# pcb_univ_3-101-0-x-rev2.net
KiCad netlist of a schematic drawn in EAGLE
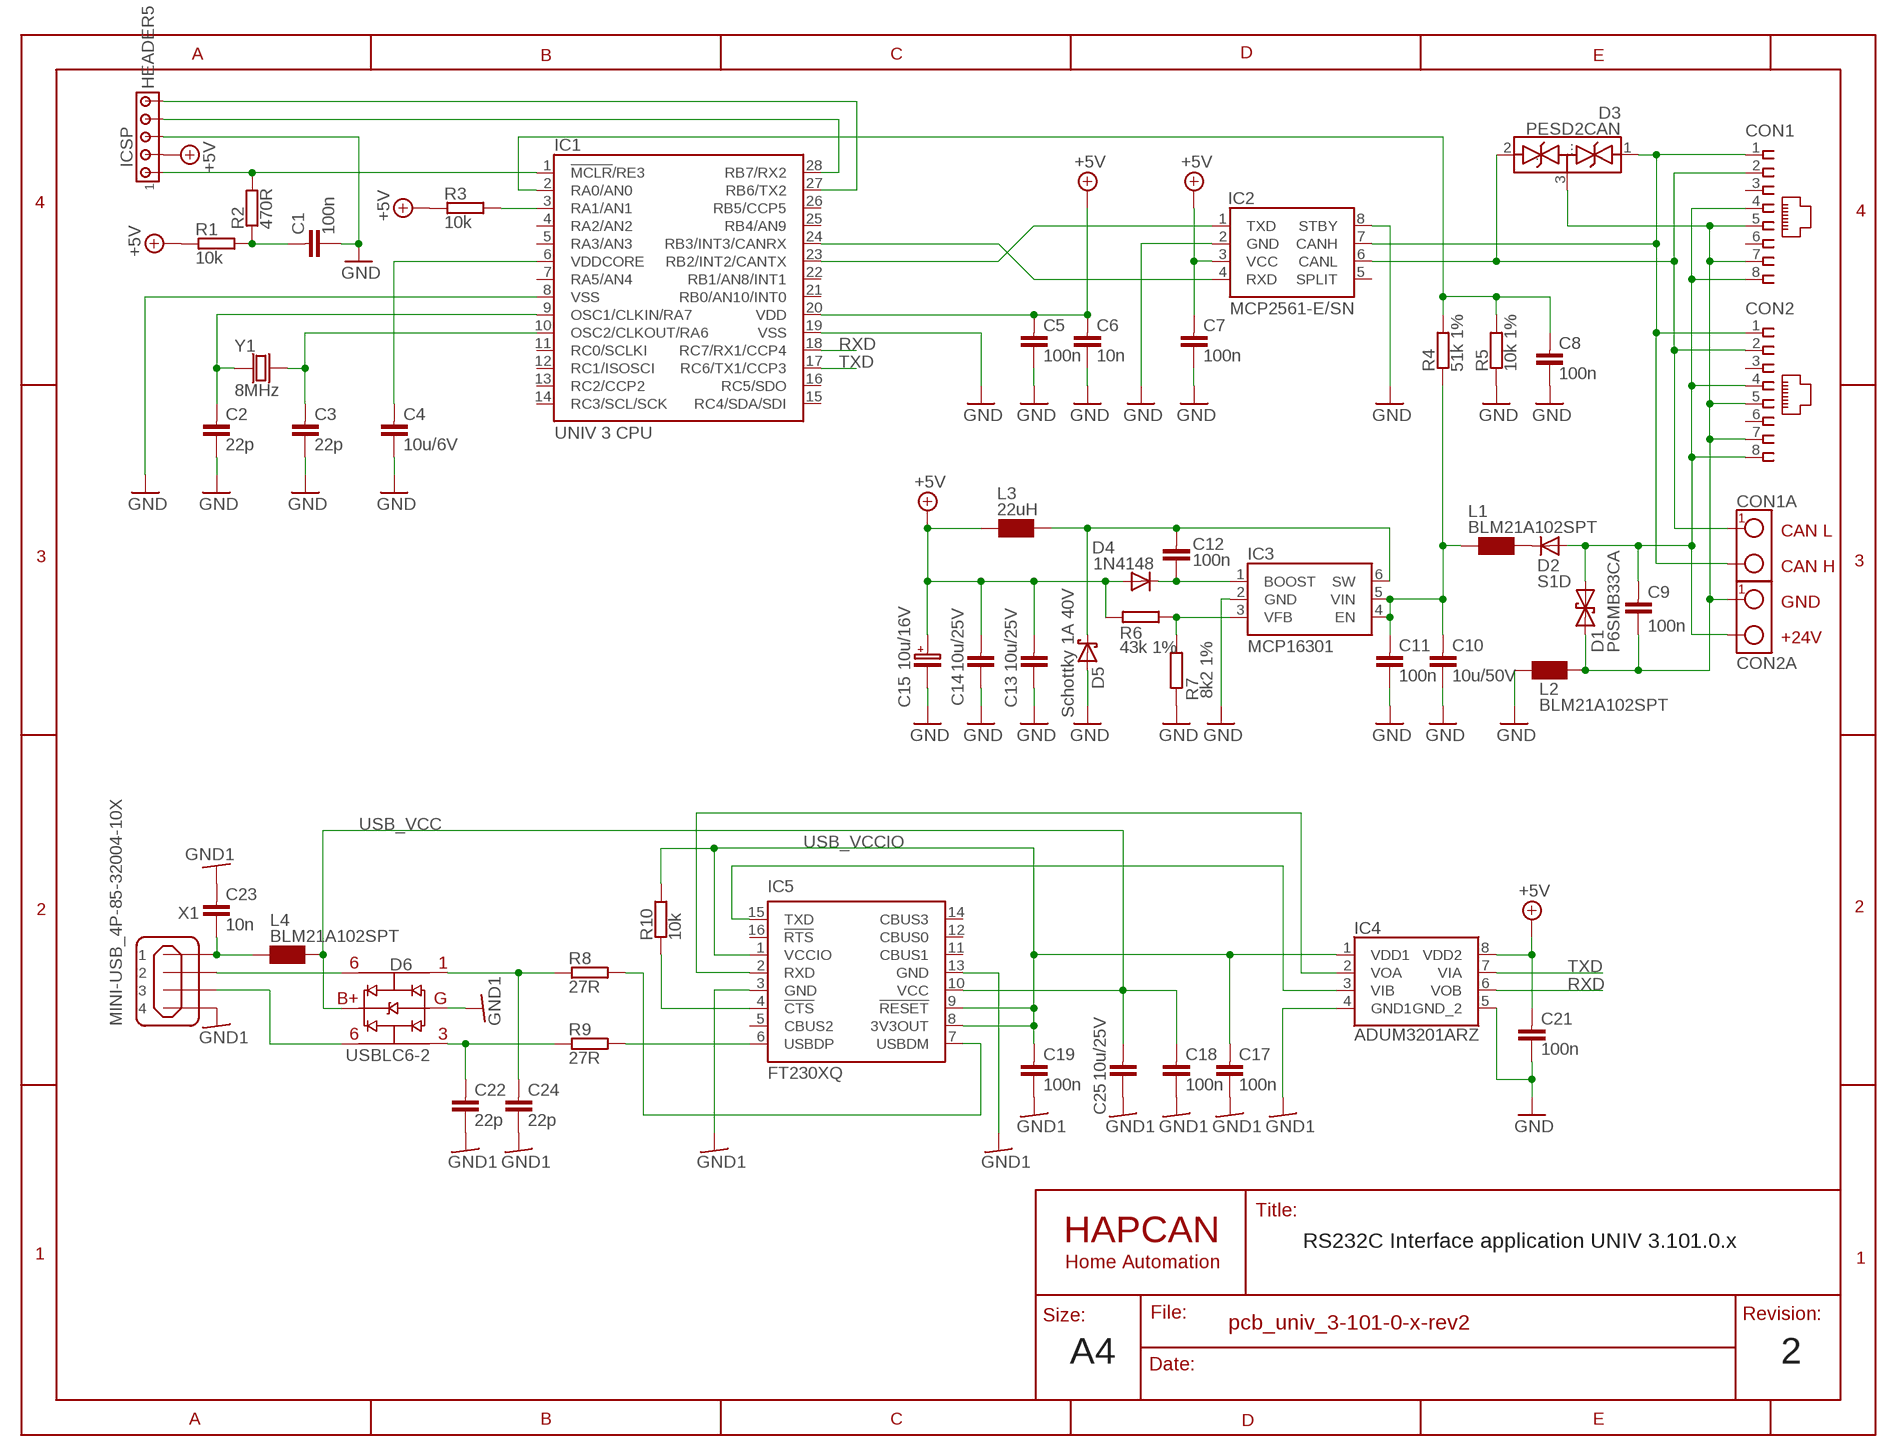
[diagram p0: schematic, sheet 1]

(export (version "E")
  (design (tool "Eeschema 10.0.6"))
  (components
    (comp (ref "C1")
      (value "100n")
      (footprint "eagle-import:0805")
      (libsource (lib "eagle-import") (part "CAPACITOR0805"))
    )
    (comp (ref "C2")
      (value "22p")
      (footprint "eagle-import:0805")
      (libsource (lib "eagle-import") (part "CAPACITOR0805"))
    )
    (comp (ref "C3")
      (value "22p")
      (footprint "eagle-import:0805")
      (libsource (lib "eagle-import") (part "CAPACITOR0805"))
    )
    (comp (ref "C4")
      (value "10u/6V")
      (footprint "eagle-import:0805")
      (libsource (lib "eagle-import") (part "CAPACITOR0805"))
    )
    (comp (ref "C5")
      (value "100n")
      (footprint "eagle-import:0805")
      (libsource (lib "eagle-import") (part "CAPACITOR0805"))
    )
    (comp (ref "C6")
      (value "10n")
      (footprint "eagle-import:0805")
      (libsource (lib "eagle-import") (part "CAPACITOR0805"))
    )
    (comp (ref "C7")
      (value "100n")
      (footprint "eagle-import:0805")
      (libsource (lib "eagle-import") (part "CAPACITOR0805"))
    )
    (comp (ref "C8")
      (value "100n")
      (footprint "eagle-import:0805")
      (libsource (lib "eagle-import") (part "CAPACITOR0805"))
    )
    (comp (ref "C9")
      (value "100n")
      (footprint "eagle-import:0805")
      (libsource (lib "eagle-import") (part "CAPACITOR0805"))
    )
    (comp (ref "C10")
      (value "10u/50V")
      (footprint "eagle-import:1210")
      (libsource (lib "eagle-import") (part "CAPACITOR1210"))
    )
    (comp (ref "C11")
      (value "100n")
      (footprint "eagle-import:0805")
      (libsource (lib "eagle-import") (part "CAPACITOR0805"))
    )
    (comp (ref "C12")
      (value "100n")
      (footprint "eagle-import:0805")
      (libsource (lib "eagle-import") (part "CAPACITOR0805"))
    )
    (comp (ref "C13")
      (value "10u/25V")
      (footprint "eagle-import:1206")
      (libsource (lib "eagle-import") (part "CAPACITOR1206"))
    )
    (comp (ref "C14")
      (value "10u/25V")
      (footprint "eagle-import:1206")
      (libsource (lib "eagle-import") (part "CAPACITOR1206"))
    )
    (comp (ref "C15")
      (value "10u/16V")
      (footprint "eagle-import:SMC_B")
      (libsource (lib "eagle-import") (part "CAPACITOR-POLARIZED-SMC_B"))
    )
    (comp (ref "C17")
      (value "100n")
      (footprint "eagle-import:0805")
      (libsource (lib "eagle-import") (part "CAPACITOR0805"))
    )
    (comp (ref "C18")
      (value "100n")
      (footprint "eagle-import:0805")
      (libsource (lib "eagle-import") (part "CAPACITOR0805"))
    )
    (comp (ref "C19")
      (value "100n")
      (footprint "eagle-import:0805")
      (libsource (lib "eagle-import") (part "CAPACITOR0805"))
    )
    (comp (ref "C21")
      (value "100n")
      (footprint "eagle-import:0805")
      (libsource (lib "eagle-import") (part "CAPACITOR0805"))
    )
    (comp (ref "C22")
      (value "22p")
      (footprint "eagle-import:0805")
      (libsource (lib "eagle-import") (part "CAPACITOR0805"))
    )
    (comp (ref "C23")
      (value "10n")
      (footprint "eagle-import:0805")
      (libsource (lib "eagle-import") (part "CAPACITOR0805"))
    )
    (comp (ref "C24")
      (value "22p")
      (footprint "eagle-import:0805")
      (libsource (lib "eagle-import") (part "CAPACITOR0805"))
    )
    (comp (ref "C25")
      (value "10u/25V")
      (footprint "eagle-import:1206")
      (libsource (lib "eagle-import") (part "CAPACITOR1206"))
    )
    (comp (ref "CON1")
      (value "RJ45-SOCKET")
      (footprint "eagle-import:RJ45-PCB-SOCKET")
      (libsource (lib "eagle-import") (part "RJ45-SOCKET"))
    )
    (comp (ref "CON1A")
      (value "TERMINAL-2")
      (footprint "eagle-import:ARK2-5X10,5MM")
      (libsource (lib "eagle-import") (part "TERMINAL-2-5X10,5MM"))
    )
    (comp (ref "CON2")
      (value "RJ45-SOCKET")
      (footprint "eagle-import:RJ45-PCB-SOCKET")
      (libsource (lib "eagle-import") (part "RJ45-SOCKET"))
    )
    (comp (ref "CON2A")
      (value "TERMINAL-2")
      (footprint "eagle-import:ARK2-5X10,5MM")
      (libsource (lib "eagle-import") (part "TERMINAL-2-5X10,5MM"))
    )
    (comp (ref "D1")
      (value "P6SMB33CA")
      (footprint "eagle-import:DO-214_TRANSIL2")
      (libsource (lib "eagle-import") (part "DIODE_TRANSIL2"))
    )
    (comp (ref "D2")
      (value "S1D")
      (footprint "eagle-import:DO-214")
      (libsource (lib "eagle-import") (part "DIODE_DO-214"))
    )
    (comp (ref "D3")
      (value "PESD2CAN")
      (footprint "eagle-import:SOT-23")
      (libsource (lib "eagle-import") (part "PESD2CANSOT-23"))
    )
    (comp (ref "D4")
      (value "1N4148")
      (footprint "eagle-import:0805")
      (libsource (lib "eagle-import") (part "DIODE_0805"))
    )
    (comp (ref "D5")
      (value "Schottky 1A 40V")
      (footprint "eagle-import:DO-214")
      (libsource (lib "eagle-import") (part "DIODE_TRANSIL1_DO214"))
    )
    (comp (ref "D6")
      (value "USBLC6-2")
      (footprint "eagle-import:SOT23-6L")
      (description "USB ESD protection")
      (fields (field (name "MFR_PART_NO") "USBLC6-2SC6"))
      (libsource (lib "eagle-import") (part "USBLC6-2"))
    )
    (comp (ref "IC1")
      (value "UNIV 3 CPU")
      (footprint "eagle-import:UNIV3CPU")
      (libsource (lib "eagle-import") (part "UNIV3CPU-I/SO"))
    )
    (comp (ref "IC2")
      (value "MCP2561-E/SN")
      (footprint "eagle-import:SO-08")
      (libsource (lib "eagle-import") (part "MCP2561-E/SN"))
    )
    (comp (ref "IC3")
      (value "MCP16301")
      (footprint "eagle-import:SOT-23-6")
      (libsource (lib "eagle-import") (part "MCP16301SOT23-6"))
    )
    (comp (ref "IC4")
      (value "ADUM3201ARZ")
      (footprint "eagle-import:SOIC127P600X175-8N")
      (fields (field (name "MF") "Analog Devices"))
      (libsource (lib "eagle-import") (part "ADUM3201ARZ"))
    )
    (comp (ref "IC5")
      (value "FT230XQ")
      (footprint "eagle-import:QFN16")
      (libsource (lib "eagle-import") (part "FT230XQ"))
    )
    (comp (ref "ICSP")
      (value "HEADER5")
      (footprint "eagle-import:SIP-5")
      (libsource (lib "eagle-import") (part "HEADER5"))
    )
    (comp (ref "L1")
      (value "BLM21A102SPT")
      (footprint "eagle-import:0805")
      (libsource (lib "eagle-import") (part "CHOKE0805"))
    )
    (comp (ref "L2")
      (value "BLM21A102SPT")
      (footprint "eagle-import:0805")
      (libsource (lib "eagle-import") (part "CHOKE0805"))
    )
    (comp (ref "L3")
      (value "22uH")
      (footprint "eagle-import:CHOKE-DER0705")
      (libsource (lib "eagle-import") (part "CHOKEDER0705"))
    )
    (comp (ref "L4")
      (value "BLM21A102SPT")
      (footprint "eagle-import:0805")
      (libsource (lib "eagle-import") (part "CHOKE0805"))
    )
    (comp (ref "R1")
      (value "10k")
      (footprint "eagle-import:0805")
      (libsource (lib "eagle-import") (part "RESISTOR0805"))
    )
    (comp (ref "R2")
      (value "470R")
      (footprint "eagle-import:0805")
      (libsource (lib "eagle-import") (part "RESISTOR0805"))
    )
    (comp (ref "R3")
      (value "10k")
      (footprint "eagle-import:0805")
      (libsource (lib "eagle-import") (part "RESISTOR0805"))
    )
    (comp (ref "R4")
      (value "51k 1%")
      (footprint "eagle-import:0805")
      (libsource (lib "eagle-import") (part "RESISTOR0805"))
    )
    (comp (ref "R5")
      (value "10k 1%")
      (footprint "eagle-import:0805")
      (libsource (lib "eagle-import") (part "RESISTOR0805"))
    )
    (comp (ref "R6")
      (value "43k 1%")
      (footprint "eagle-import:0805")
      (libsource (lib "eagle-import") (part "RESISTOR0805"))
    )
    (comp (ref "R7")
      (value "8k2 1%")
      (footprint "eagle-import:0805")
      (libsource (lib "eagle-import") (part "RESISTOR0805"))
    )
    (comp (ref "R8")
      (value "27R")
      (footprint "eagle-import:0805")
      (libsource (lib "eagle-import") (part "RESISTOR0805"))
    )
    (comp (ref "R9")
      (value "27R")
      (footprint "eagle-import:0805")
      (libsource (lib "eagle-import") (part "RESISTOR0805"))
    )
    (comp (ref "R10")
      (value "10k")
      (footprint "eagle-import:0805")
      (libsource (lib "eagle-import") (part "RESISTOR0805"))
    )
    (comp (ref "X1")
      (value "MINI-USB_4P-85-32004-10X")
      (footprint "eagle-import:85-32004-10X")
      (libsource (lib "eagle-import") (part "MINI-USB_4P-85-32004-10X"))
    )
    (comp (ref "Y1")
      (value "8MHz")
      (footprint "eagle-import:CRYSTAL-HC49V")
      (libsource (lib "eagle-import") (part "CRYSTAL-HC49V"))
    )
  )
  (nets
    (net (code "1") (name "+5V") (class "Default")
      (node (ref "C13") (pin "1") (pinfunction "1_1") (pintype "passive"))
      (node (ref "C14") (pin "1") (pinfunction "1_1") (pintype "passive"))
      (node (ref "C15") (pin "+") (pinfunction "1_+") (pintype "passive"))
      (node (ref "C21") (pin "1") (pinfunction "1_1") (pintype "passive"))
      (node (ref "C5") (pin "1") (pinfunction "1_1") (pintype "passive"))
      (node (ref "C6") (pin "1") (pinfunction "1_1") (pintype "passive"))
      (node (ref "C7") (pin "1") (pinfunction "1_1") (pintype "passive"))
      (node (ref "D4") (pin "2") (pinfunction "A_2") (pintype "passive"))
      (node (ref "IC1") (pin "20") (pinfunction "VDD_20") (pintype "bidirectional"))
      (node (ref "IC2") (pin "3") (pinfunction "VCC_3") (pintype "bidirectional"))
      (node (ref "IC4") (pin "8") (pinfunction "VDD2_8") (pintype "bidirectional"))
      (node (ref "ICSP") (pin "2") (pinfunction "2_2") (pintype "passive"))
      (node (ref "L3") (pin "1") (pinfunction "1_1") (pintype "passive"))
      (node (ref "R1") (pin "1") (pinfunction "1_1") (pintype "passive"))
      (node (ref "R3") (pin "1") (pinfunction "1_1") (pintype "passive"))
      (node (ref "R6") (pin "1") (pinfunction "1_1") (pintype "passive"))
    )
    (net (code "2") (name "/RXD") (class "Default")
      (node (ref "IC1") (pin "18") (pinfunction "RC7/RX1/CCP4_18") (pintype "bidirectional"))
      (node (ref "IC4") (pin "6") (pinfunction "VOB_6") (pintype "bidirectional"))
    )
    (net (code "3") (name "/TXD") (class "Default")
      (node (ref "IC1") (pin "17") (pinfunction "RC6/TX1/CCP3_17") (pintype "bidirectional"))
      (node (ref "IC4") (pin "7") (pinfunction "VIA_7") (pintype "bidirectional"))
    )
    (net (code "4") (name "/USB_VCC") (class "Default")
      (node (ref "C18") (pin "1") (pinfunction "1_1") (pintype "passive"))
      (node (ref "C25") (pin "1") (pinfunction "1_1") (pintype "passive"))
      (node (ref "D6") (pin "5") (pinfunction "B+_5") (pintype "bidirectional"))
      (node (ref "IC5") (pin "10") (pinfunction "VCC_10") (pintype "power_in"))
      (node (ref "L4") (pin "1") (pinfunction "1_1") (pintype "passive"))
    )
    (net (code "5") (name "/USB_VCCIO") (class "Default")
      (node (ref "C17") (pin "1") (pinfunction "1_1") (pintype "passive"))
      (node (ref "C19") (pin "1") (pinfunction "1_1") (pintype "passive"))
      (node (ref "IC4") (pin "1") (pinfunction "VDD1_1") (pintype "bidirectional"))
      (node (ref "IC5") (pin "1") (pinfunction "VCCIO_1") (pintype "power_in"))
      (node (ref "IC5") (pin "8") (pinfunction "3V3OUT_8") (pintype "output"))
      (node (ref "IC5") (pin "9") (pinfunction "~{RESET}_9") (pintype "input"))
      (node (ref "R10") (pin "2") (pinfunction "2_2") (pintype "passive"))
    )
    (net (code "6") (name "GND") (class "Default")
      (node (ref "C1") (pin "2") (pinfunction "2_2") (pintype "passive"))
      (node (ref "C10") (pin "2") (pinfunction "2_2") (pintype "passive"))
      (node (ref "C11") (pin "2") (pinfunction "2_2") (pintype "passive"))
      (node (ref "C13") (pin "2") (pinfunction "2_2") (pintype "passive"))
      (node (ref "C14") (pin "2") (pinfunction "2_2") (pintype "passive"))
      (node (ref "C15") (pin "-") (pinfunction "2_-") (pintype "passive"))
      (node (ref "C2") (pin "2") (pinfunction "2_2") (pintype "passive"))
      (node (ref "C21") (pin "2") (pinfunction "2_2") (pintype "passive"))
      (node (ref "C3") (pin "2") (pinfunction "2_2") (pintype "passive"))
      (node (ref "C4") (pin "2") (pinfunction "2_2") (pintype "passive"))
      (node (ref "C5") (pin "2") (pinfunction "2_2") (pintype "passive"))
      (node (ref "C6") (pin "2") (pinfunction "2_2") (pintype "passive"))
      (node (ref "C7") (pin "2") (pinfunction "2_2") (pintype "passive"))
      (node (ref "C8") (pin "2") (pinfunction "2_2") (pintype "passive"))
      (node (ref "D5") (pin "A") (pinfunction "A_A") (pintype "passive"))
      (node (ref "IC1") (pin "19") (pinfunction "VSS_19") (pintype "bidirectional"))
      (node (ref "IC1") (pin "8") (pinfunction "VSS_8") (pintype "bidirectional"))
      (node (ref "IC2") (pin "2") (pinfunction "GND_2") (pintype "bidirectional"))
      (node (ref "IC2") (pin "8") (pinfunction "STBY_8") (pintype "bidirectional"))
      (node (ref "IC3") (pin "2") (pinfunction "GND_2") (pintype "bidirectional"))
      (node (ref "IC4") (pin "5") (pinfunction "GND_2_5") (pintype "bidirectional"))
      (node (ref "ICSP") (pin "3") (pinfunction "3_3") (pintype "passive"))
      (node (ref "L2") (pin "1") (pinfunction "1_1") (pintype "passive"))
      (node (ref "R5") (pin "1") (pinfunction "1_1") (pintype "passive"))
      (node (ref "R7") (pin "1") (pinfunction "1_1") (pintype "passive"))
    )
    (net (code "7") (name "GND1") (class "Default")
      (node (ref "C17") (pin "2") (pinfunction "2_2") (pintype "passive"))
      (node (ref "C18") (pin "2") (pinfunction "2_2") (pintype "passive"))
      (node (ref "C19") (pin "2") (pinfunction "2_2") (pintype "passive"))
      (node (ref "C22") (pin "2") (pinfunction "2_2") (pintype "passive"))
      (node (ref "C23") (pin "1") (pinfunction "1_1") (pintype "passive"))
      (node (ref "C24") (pin "2") (pinfunction "2_2") (pintype "passive"))
      (node (ref "C25") (pin "2") (pinfunction "2_2") (pintype "passive"))
      (node (ref "D6") (pin "2") (pinfunction "G_2") (pintype "bidirectional"))
      (node (ref "IC4") (pin "4") (pinfunction "GND1_4") (pintype "bidirectional"))
      (node (ref "IC5") (pin "13") (pinfunction "GND_13") (pintype "power_in"))
      (node (ref "IC5") (pin "3") (pinfunction "GND_3") (pintype "power_in"))
      (node (ref "X1") (pin "4") (pinfunction "4_4") (pintype "passive"))
    )
    (net (code "8") (name "Net-(C1-Pad1)") (class "Default")
      (node (ref "C1") (pin "1") (pinfunction "1_1") (pintype "passive"))
      (node (ref "R1") (pin "2") (pinfunction "2_2") (pintype "passive"))
      (node (ref "R2") (pin "1") (pinfunction "1_1") (pintype "passive"))
    )
    (net (code "9") (name "Net-(C22-Pad1)") (class "Default")
      (node (ref "C22") (pin "1") (pinfunction "1_1") (pintype "passive"))
      (node (ref "D6") (pin "3") (pinfunction "3_3") (pintype "bidirectional"))
      (node (ref "R9") (pin "1") (pinfunction "1_1") (pintype "passive"))
    )
    (net (code "10") (name "Net-(C23-Pad2)") (class "Default")
      (node (ref "C23") (pin "2") (pinfunction "2_2") (pintype "passive"))
      (node (ref "L4") (pin "2") (pinfunction "2_2") (pintype "passive"))
      (node (ref "X1") (pin "1") (pinfunction "1_1") (pintype "passive"))
    )
    (net (code "11") (name "Net-(C24-Pad1)") (class "Default")
      (node (ref "C24") (pin "1") (pinfunction "1_1") (pintype "passive"))
      (node (ref "D6") (pin "1") (pinfunction "1_1") (pintype "bidirectional"))
      (node (ref "R8") (pin "1") (pinfunction "1_1") (pintype "passive"))
    )
    (net (code "12") (name "Net-(D1-1)") (class "Default")
      (node (ref "C9") (pin "1") (pinfunction "1_1") (pintype "passive"))
      (node (ref "CON1") (pin "4") (pinfunction "4_4") (pintype "passive"))
      (node (ref "CON1") (pin "8") (pinfunction "8_8") (pintype "passive"))
      (node (ref "CON2") (pin "4") (pinfunction "4_4") (pintype "passive"))
      (node (ref "CON2") (pin "8") (pinfunction "8_8") (pintype "passive"))
      (node (ref "CON2A") (pin "2") (pinfunction "2_2") (pintype "passive"))
      (node (ref "D1") (pin "A") (pinfunction "1_A") (pintype "passive"))
      (node (ref "D2") (pin "A") (pinfunction "A_A") (pintype "passive"))
    )
    (net (code "13") (name "Net-(D1-2)") (class "Default")
      (node (ref "C9") (pin "2") (pinfunction "2_2") (pintype "passive"))
      (node (ref "CON1") (pin "5") (pinfunction "5_5") (pintype "passive"))
      (node (ref "CON1") (pin "7") (pinfunction "7_7") (pintype "passive"))
      (node (ref "CON2") (pin "5") (pinfunction "5_5") (pintype "passive"))
      (node (ref "CON2") (pin "7") (pinfunction "7_7") (pintype "passive"))
      (node (ref "CON2A") (pin "1") (pinfunction "1_1") (pintype "passive"))
      (node (ref "D1") (pin "C") (pinfunction "2_C") (pintype "passive"))
      (node (ref "D3") (pin "3") (pinfunction "..._3") (pintype "bidirectional"))
      (node (ref "L2") (pin "2") (pinfunction "2_2") (pintype "passive"))
    )
    (net (code "14") (name "Net-(D2-PadC)") (class "Default")
      (node (ref "D2") (pin "C") (pinfunction "C_C") (pintype "passive"))
      (node (ref "L1") (pin "2") (pinfunction "2_2") (pintype "passive"))
    )
    (net (code "15") (name "Net-(D3-.)") (class "Default")
      (node (ref "CON1") (pin "1") (pinfunction "1_1") (pintype "passive"))
      (node (ref "CON1A") (pin "2") (pinfunction "2_2") (pintype "passive"))
      (node (ref "CON2") (pin "1") (pinfunction "1_1") (pintype "passive"))
      (node (ref "D3") (pin "1") (pinfunction "._1") (pintype "bidirectional"))
      (node (ref "IC2") (pin "7") (pinfunction "CANH_7") (pintype "bidirectional"))
    )
    (net (code "16") (name "Net-(D3-..)") (class "Default")
      (node (ref "CON1") (pin "2") (pinfunction "2_2") (pintype "passive"))
      (node (ref "CON1A") (pin "1") (pinfunction "1_1") (pintype "passive"))
      (node (ref "CON2") (pin "2") (pinfunction "2_2") (pintype "passive"))
      (node (ref "D3") (pin "2") (pinfunction ".._2") (pintype "bidirectional"))
      (node (ref "IC2") (pin "6") (pinfunction "CANL_6") (pintype "bidirectional"))
    )
    (net (code "17") (name "Net-(D4-C)") (class "Default")
      (node (ref "C12") (pin "2") (pinfunction "2_2") (pintype "passive"))
      (node (ref "D4") (pin "1") (pinfunction "C_1") (pintype "passive"))
      (node (ref "IC3") (pin "1") (pinfunction "BOOST_1") (pintype "bidirectional"))
    )
    (net (code "18") (name "Net-(D6-Pad4)") (class "Default")
      (node (ref "D6") (pin "4") (pinfunction "4_4") (pintype "bidirectional"))
      (node (ref "X1") (pin "3") (pinfunction "3_3") (pintype "passive"))
    )
    (net (code "19") (name "Net-(D6-Pad6)") (class "Default")
      (node (ref "D6") (pin "6") (pinfunction "6_6") (pintype "bidirectional"))
      (node (ref "X1") (pin "2") (pinfunction "2_2") (pintype "passive"))
    )
    (net (code "20") (name "Net-(IC1-OSC1{slash}CLKIN{slash}RA7)") (class "Default")
      (node (ref "C2") (pin "1") (pinfunction "1_1") (pintype "passive"))
      (node (ref "IC1") (pin "9") (pinfunction "OSC1/CLKIN/RA7_9") (pintype "bidirectional"))
      (node (ref "Y1") (pin "1") (pinfunction "1_1") (pintype "passive"))
    )
    (net (code "21") (name "Net-(IC1-OSC2{slash}CLKOUT{slash}RA6)") (class "Default")
      (node (ref "C3") (pin "1") (pinfunction "1_1") (pintype "passive"))
      (node (ref "IC1") (pin "10") (pinfunction "OSC2/CLKOUT/RA6_10") (pintype "bidirectional"))
      (node (ref "Y1") (pin "2") (pinfunction "2_2") (pintype "passive"))
    )
    (net (code "22") (name "Net-(IC1-RA0{slash}AN0)") (class "Default")
      (node (ref "C8") (pin "1") (pinfunction "1_1") (pintype "passive"))
      (node (ref "IC1") (pin "2") (pinfunction "RA0/AN0_2") (pintype "bidirectional"))
      (node (ref "R4") (pin "2") (pinfunction "2_2") (pintype "passive"))
      (node (ref "R5") (pin "2") (pinfunction "2_2") (pintype "passive"))
    )
    (net (code "23") (name "Net-(IC1-RA1{slash}AN1)") (class "Default")
      (node (ref "IC1") (pin "3") (pinfunction "RA1/AN1_3") (pintype "bidirectional"))
      (node (ref "R3") (pin "2") (pinfunction "2_2") (pintype "passive"))
    )
    (net (code "24") (name "Net-(IC1-RB2{slash}INT2{slash}CANTX)") (class "Default")
      (node (ref "IC1") (pin "23") (pinfunction "RB2/INT2/CANTX_23") (pintype "bidirectional"))
      (node (ref "IC2") (pin "1") (pinfunction "TXD_1") (pintype "bidirectional"))
    )
    (net (code "25") (name "Net-(IC1-RB3{slash}INT3{slash}CANRX)") (class "Default")
      (node (ref "IC1") (pin "24") (pinfunction "RB3/INT3/CANRX_24") (pintype "bidirectional"))
      (node (ref "IC2") (pin "4") (pinfunction "RXD_4") (pintype "bidirectional"))
    )
    (net (code "26") (name "Net-(IC1-RB6{slash}TX2)") (class "Default")
      (node (ref "IC1") (pin "27") (pinfunction "RB6/TX2_27") (pintype "bidirectional"))
      (node (ref "ICSP") (pin "5") (pinfunction "5_5") (pintype "passive"))
    )
    (net (code "27") (name "Net-(IC1-RB7{slash}RX2)") (class "Default")
      (node (ref "IC1") (pin "28") (pinfunction "RB7/RX2_28") (pintype "bidirectional"))
      (node (ref "ICSP") (pin "4") (pinfunction "4_4") (pintype "passive"))
    )
    (net (code "28") (name "Net-(IC1-VDDCORE)") (class "Default")
      (node (ref "C4") (pin "1") (pinfunction "1_1") (pintype "passive"))
      (node (ref "IC1") (pin "6") (pinfunction "VDDCORE_6") (pintype "bidirectional"))
    )
    (net (code "29") (name "Net-(IC1-~{MCLR}{slash}RE3)") (class "Default")
      (node (ref "IC1") (pin "1") (pinfunction "~{MCLR}/RE3_1") (pintype "bidirectional"))
      (node (ref "ICSP") (pin "1") (pinfunction "1_1") (pintype "passive"))
      (node (ref "R2") (pin "2") (pinfunction "2_2") (pintype "passive"))
    )
    (net (code "30") (name "Net-(IC3-EN)") (class "Default")
      (node (ref "C10") (pin "1") (pinfunction "1_1") (pintype "passive"))
      (node (ref "C11") (pin "1") (pinfunction "1_1") (pintype "passive"))
      (node (ref "IC3") (pin "4") (pinfunction "EN_4") (pintype "bidirectional"))
      (node (ref "IC3") (pin "5") (pinfunction "VIN_5") (pintype "bidirectional"))
      (node (ref "L1") (pin "1") (pinfunction "1_1") (pintype "passive"))
      (node (ref "R4") (pin "1") (pinfunction "1_1") (pintype "passive"))
    )
    (net (code "31") (name "Net-(IC3-SW)") (class "Default")
      (node (ref "C12") (pin "1") (pinfunction "1_1") (pintype "passive"))
      (node (ref "D5") (pin "C") (pinfunction "C_C") (pintype "passive"))
      (node (ref "IC3") (pin "6") (pinfunction "SW_6") (pintype "bidirectional"))
      (node (ref "L3") (pin "2") (pinfunction "2_2") (pintype "passive"))
    )
    (net (code "32") (name "Net-(IC3-VFB)") (class "Default")
      (node (ref "IC3") (pin "3") (pinfunction "VFB_3") (pintype "bidirectional"))
      (node (ref "R6") (pin "2") (pinfunction "2_2") (pintype "passive"))
      (node (ref "R7") (pin "2") (pinfunction "2_2") (pintype "passive"))
    )
    (net (code "33") (name "Net-(IC4-VIB)") (class "Default")
      (node (ref "IC4") (pin "3") (pinfunction "VIB_3") (pintype "bidirectional"))
      (node (ref "IC5") (pin "15") (pinfunction "TXD_15") (pintype "output"))
    )
    (net (code "34") (name "Net-(IC4-VOA)") (class "Default")
      (node (ref "IC4") (pin "2") (pinfunction "VOA_2") (pintype "bidirectional"))
      (node (ref "IC5") (pin "2") (pinfunction "RXD_2") (pintype "input"))
    )
    (net (code "35") (name "Net-(IC5-USBDM)") (class "Default")
      (node (ref "IC5") (pin "7") (pinfunction "USBDM_7") (pintype "input"))
      (node (ref "R8") (pin "2") (pinfunction "2_2") (pintype "passive"))
    )
    (net (code "36") (name "Net-(IC5-USBDP)") (class "Default")
      (node (ref "IC5") (pin "6") (pinfunction "USBDP_6") (pintype "input"))
      (node (ref "R9") (pin "2") (pinfunction "2_2") (pintype "passive"))
    )
    (net (code "37") (name "Net-(IC5-~{CTS})") (class "Default")
      (node (ref "IC5") (pin "4") (pinfunction "~{CTS}_4") (pintype "input"))
      (node (ref "R10") (pin "1") (pinfunction "1_1") (pintype "passive"))
    )
    (net (code "38") (name "unconnected-(CON1-Pad3)") (class "Default")
      (node (ref "CON1") (pin "3") (pinfunction "3_3") (pintype "passive"))
    )
    (net (code "39") (name "unconnected-(CON1-Pad6)") (class "Default")
      (node (ref "CON1") (pin "6") (pinfunction "6_6") (pintype "passive"))
    )
    (net (code "40") (name "unconnected-(CON2-Pad3)") (class "Default")
      (node (ref "CON2") (pin "3") (pinfunction "3_3") (pintype "passive"))
    )
    (net (code "41") (name "unconnected-(CON2-Pad6)") (class "Default")
      (node (ref "CON2") (pin "6") (pinfunction "6_6") (pintype "passive"))
    )
    (net (code "42") (name "unconnected-(IC1-RA2{slash}AN2-Pad4)") (class "Default")
      (node (ref "IC1") (pin "4") (pinfunction "RA2/AN2_4") (pintype "bidirectional"))
    )
    (net (code "43") (name "unconnected-(IC1-RA3{slash}AN3-Pad5)") (class "Default")
      (node (ref "IC1") (pin "5") (pinfunction "RA3/AN3_5") (pintype "bidirectional"))
    )
    (net (code "44") (name "unconnected-(IC1-RA5{slash}AN4-Pad7)") (class "Default")
      (node (ref "IC1") (pin "7") (pinfunction "RA5/AN4_7") (pintype "bidirectional"))
    )
    (net (code "45") (name "unconnected-(IC1-RB0{slash}AN10{slash}INT0-Pad21)") (class "Default")
      (node (ref "IC1") (pin "21") (pinfunction "RB0/AN10/INT0_21") (pintype "bidirectional"))
    )
    (net (code "46") (name "unconnected-(IC1-RB1{slash}AN8{slash}INT1-Pad22)") (class "Default")
      (node (ref "IC1") (pin "22") (pinfunction "RB1/AN8/INT1_22") (pintype "bidirectional"))
    )
    (net (code "47") (name "unconnected-(IC1-RB4{slash}AN9-Pad25)") (class "Default")
      (node (ref "IC1") (pin "25") (pinfunction "RB4/AN9_25") (pintype "bidirectional"))
    )
    (net (code "48") (name "unconnected-(IC1-RB5{slash}CCP5-Pad26)") (class "Default")
      (node (ref "IC1") (pin "26") (pinfunction "RB5/CCP5_26") (pintype "bidirectional"))
    )
    (net (code "49") (name "unconnected-(IC1-RC0{slash}SCLKI-Pad11)") (class "Default")
      (node (ref "IC1") (pin "11") (pinfunction "RC0/SCLKI_11") (pintype "bidirectional"))
    )
    (net (code "50") (name "unconnected-(IC1-RC1{slash}ISOSCI-Pad12)") (class "Default")
      (node (ref "IC1") (pin "12") (pinfunction "RC1/ISOSCI_12") (pintype "bidirectional"))
    )
    (net (code "51") (name "unconnected-(IC1-RC2{slash}CCP2-Pad13)") (class "Default")
      (node (ref "IC1") (pin "13") (pinfunction "RC2/CCP2_13") (pintype "bidirectional"))
    )
    (net (code "52") (name "unconnected-(IC1-RC3{slash}SCL{slash}SCK-Pad14)") (class "Default")
      (node (ref "IC1") (pin "14") (pinfunction "RC3/SCL/SCK_14") (pintype "bidirectional"))
    )
    (net (code "53") (name "unconnected-(IC1-RC4{slash}SDA{slash}SDI-Pad15)") (class "Default")
      (node (ref "IC1") (pin "15") (pinfunction "RC4/SDA/SDI_15") (pintype "bidirectional"))
    )
    (net (code "54") (name "unconnected-(IC1-RC5{slash}SDO-Pad16)") (class "Default")
      (node (ref "IC1") (pin "16") (pinfunction "RC5/SDO_16") (pintype "bidirectional"))
    )
    (net (code "55") (name "unconnected-(IC2-SPLIT-Pad5)") (class "Default")
      (node (ref "IC2") (pin "5") (pinfunction "SPLIT_5") (pintype "bidirectional"))
    )
    (net (code "56") (name "unconnected-(IC5-CBUS0-Pad12)") (class "Default")
      (node (ref "IC5") (pin "12") (pinfunction "CBUS0_12") (pintype "bidirectional"))
    )
    (net (code "57") (name "unconnected-(IC5-CBUS1-Pad11)") (class "Default")
      (node (ref "IC5") (pin "11") (pinfunction "CBUS1_11") (pintype "bidirectional"))
    )
    (net (code "58") (name "unconnected-(IC5-CBUS2-Pad5)") (class "Default")
      (node (ref "IC5") (pin "5") (pinfunction "CBUS2_5") (pintype "bidirectional"))
    )
    (net (code "59") (name "unconnected-(IC5-CBUS3-Pad14)") (class "Default")
      (node (ref "IC5") (pin "14") (pinfunction "CBUS3_14") (pintype "bidirectional"))
    )
    (net (code "60") (name "unconnected-(IC5-~{RTS}-Pad16)") (class "Default")
      (node (ref "IC5") (pin "16") (pinfunction "~{RTS}_16") (pintype "output"))
    )
  )
)
